# reflow_oven_main.net
KiCad netlist of a schematic drawn in EAGLE
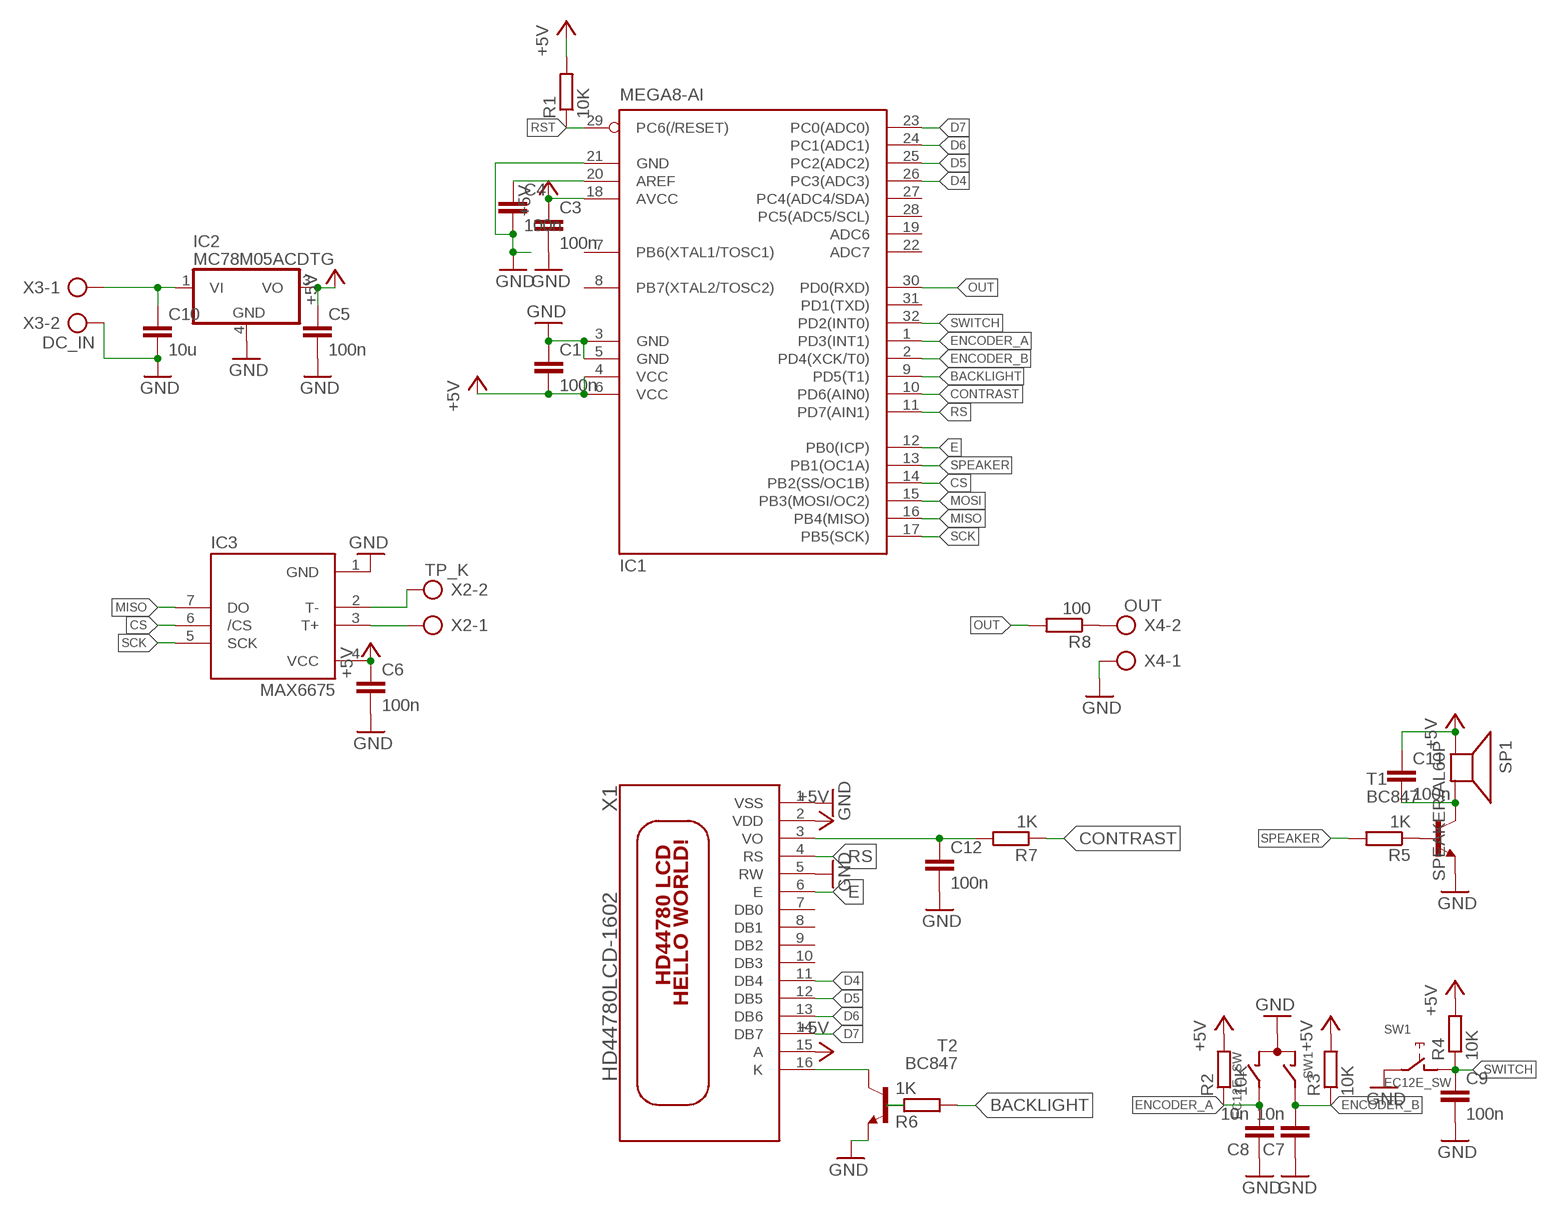
[diagram p0: schematic, sheet 1]

(export (version "E")
  (design (tool "Eeschema 10.0.6"))
  (components
    (comp (ref "C1")
      (value "100n")
      (footprint "eagle-import:C0603")
      (libsource (lib "eagle-import") (part "C-EUC0603"))
    )
    (comp (ref "C3")
      (value "100n")
      (footprint "eagle-import:C0603")
      (libsource (lib "eagle-import") (part "C-EUC0603"))
    )
    (comp (ref "C4")
      (value "100n")
      (footprint "eagle-import:C0603")
      (libsource (lib "eagle-import") (part "C-EUC0603"))
    )
    (comp (ref "C5")
      (value "100n")
      (footprint "eagle-import:C0603")
      (libsource (lib "eagle-import") (part "C-EUC0603"))
    )
    (comp (ref "C6")
      (value "100n")
      (footprint "eagle-import:C0603")
      (libsource (lib "eagle-import") (part "C-EUC0603"))
    )
    (comp (ref "C7")
      (value "10n")
      (footprint "eagle-import:C0603")
      (libsource (lib "eagle-import") (part "C-EUC0603"))
    )
    (comp (ref "C8")
      (value "10n")
      (footprint "eagle-import:C0603")
      (libsource (lib "eagle-import") (part "C-EUC0603"))
    )
    (comp (ref "C9")
      (value "100n")
      (footprint "eagle-import:C0603")
      (libsource (lib "eagle-import") (part "C-EUC0603"))
    )
    (comp (ref "C10")
      (value "10u")
      (footprint "eagle-import:C0805")
      (libsource (lib "eagle-import") (part "C-EUC0805"))
    )
    (comp (ref "C11")
      (value "100n")
      (footprint "eagle-import:C0603")
      (libsource (lib "eagle-import") (part "C-EUC0603"))
    )
    (comp (ref "C12")
      (value "100n")
      (footprint "eagle-import:C0603")
      (libsource (lib "eagle-import") (part "C-EUC0603"))
    )
    (comp (ref "IC1")
      (value "MEGA8-AI")
      (footprint "eagle-import:TQFP32-08")
      (fields (field (name "MPN") "ATMEGA8-16AU"))
      (libsource (lib "eagle-import") (part "MEGA8-AI"))
    )
    (comp (ref "IC2")
      (value "MC78M05ACDTG")
      (footprint "eagle-import:DPACK_3")
      (libsource (lib "eagle-import") (part "MC78M05ACDTG"))
    )
    (comp (ref "IC3")
      (value "MAX6675")
      (footprint "eagle-import:SO08")
      (libsource (lib "eagle-import") (part "MAX6675"))
    )
    (comp (ref "R1")
      (value "10K")
      (footprint "eagle-import:R0603")
      (libsource (lib "eagle-import") (part "R-EU_R0603"))
    )
    (comp (ref "R2")
      (value "10K")
      (footprint "eagle-import:R0603")
      (libsource (lib "eagle-import") (part "R-EU_R0603"))
    )
    (comp (ref "R3")
      (value "10K")
      (footprint "eagle-import:R0603")
      (libsource (lib "eagle-import") (part "R-EU_R0603"))
    )
    (comp (ref "R4")
      (value "10K")
      (footprint "eagle-import:R0603")
      (libsource (lib "eagle-import") (part "R-EU_R0603"))
    )
    (comp (ref "R5")
      (value "1K")
      (footprint "eagle-import:R0603")
      (libsource (lib "eagle-import") (part "R-EU_R0603"))
    )
    (comp (ref "R6")
      (value "1K")
      (footprint "eagle-import:R0603")
      (libsource (lib "eagle-import") (part "R-EU_R0603"))
    )
    (comp (ref "R7")
      (value "1K")
      (footprint "eagle-import:R0603")
      (libsource (lib "eagle-import") (part "R-EU_R0603"))
    )
    (comp (ref "R8")
      (value "100")
      (footprint "eagle-import:R0603")
      (libsource (lib "eagle-import") (part "R-EU_R0603"))
    )
    (comp (ref "SP1")
      (value "SPEAKER/AL60P")
      (footprint "eagle-import:AL60P")
      (libsource (lib "eagle-import") (part "SPEAKER/AL60P"))
    )
    (comp (ref "SW1")
      (value "EC12E_SW")
      (footprint "eagle-import:ALPS_EC12E_SW")
      (fields (field (name "MPN") "EC12E2424407"))
      (libsource (lib "eagle-import") (part "EC12E_SW"))
    )
    (comp (ref "T1")
      (value "BC847")
      (footprint "eagle-import:SOT23")
      (libsource (lib "eagle-import") (part "BC847"))
    )
    (comp (ref "T2")
      (value "BC847")
      (footprint "eagle-import:SOT23")
      (libsource (lib "eagle-import") (part "BC847"))
    )
    (comp (ref "X1")
      (value "HD44780LCD-1602")
      (footprint "eagle-import:LCD1602")
      (libsource (lib "eagle-import") (part "HD44780LCD-1602"))
    )
    (comp (ref "X2")
      (value "TP_K")
      (footprint "eagle-import:AK500_2")
      (libsource (lib "eagle-import") (part "AK500/2"))
    )
    (comp (ref "X3")
      (value "DC_IN")
      (footprint "eagle-import:AK500_2")
      (libsource (lib "eagle-import") (part "AK500/2"))
    )
    (comp (ref "X4")
      (value "OUT")
      (footprint "eagle-import:AK500_2")
      (libsource (lib "eagle-import") (part "AK500/2"))
    )
  )
  (nets
    (net (code "1") (name "+5V") (class "Default")
      (node (ref "C1") (pin "2") (pinfunction "2_2") (pintype "passive"))
      (node (ref "C11") (pin "1") (pinfunction "1_1") (pintype "passive"))
      (node (ref "C3") (pin "1") (pinfunction "1_1") (pintype "passive"))
      (node (ref "C5") (pin "1") (pinfunction "1_1") (pintype "passive"))
      (node (ref "C6") (pin "1") (pinfunction "1_1") (pintype "passive"))
      (node (ref "IC1") (pin "18") (pinfunction "AVCC_18") (pintype "power_in"))
      (node (ref "IC1") (pin "4") (pinfunction "VCC_4") (pintype "power_in"))
      (node (ref "IC1") (pin "6") (pinfunction "VCC_6") (pintype "power_in"))
      (node (ref "IC2") (pin "3") (pinfunction "VO_3") (pintype "passive"))
      (node (ref "IC3") (pin "4") (pinfunction "VCC_4") (pintype "power_in"))
      (node (ref "R1") (pin "2") (pinfunction "2_2") (pintype "passive"))
      (node (ref "R2") (pin "2") (pinfunction "2_2") (pintype "passive"))
      (node (ref "R3") (pin "2") (pinfunction "2_2") (pintype "passive"))
      (node (ref "R4") (pin "2") (pinfunction "2_2") (pintype "passive"))
      (node (ref "SP1") (pin "1") (pinfunction "+_1") (pintype "passive"))
      (node (ref "X1") (pin "15") (pinfunction "A_15") (pintype "input"))
      (node (ref "X1") (pin "2") (pinfunction "VDD_2") (pintype "power_in"))
    )
    (net (code "2") (name "BACKLIGHT") (class "Default")
      (node (ref "IC1") (pin "9") (pinfunction "PD5(T1)_9") (pintype "bidirectional"))
      (node (ref "R6") (pin "2") (pinfunction "2_2") (pintype "passive"))
    )
    (net (code "3") (name "CONTRAST") (class "Default")
      (node (ref "IC1") (pin "10") (pinfunction "PD6(AIN0)_10") (pintype "bidirectional"))
      (node (ref "R7") (pin "1") (pinfunction "1_1") (pintype "passive"))
    )
    (net (code "4") (name "CS") (class "Default")
      (node (ref "IC1") (pin "14") (pinfunction "PB2(SS/OC1B)_14") (pintype "bidirectional"))
      (node (ref "IC3") (pin "6") (pinfunction "/CS_6") (pintype "input"))
    )
    (net (code "5") (name "D4") (class "Default")
      (node (ref "IC1") (pin "26") (pinfunction "PC3(ADC3)_26") (pintype "bidirectional"))
      (node (ref "X1") (pin "11") (pinfunction "DB4_11") (pintype "bidirectional"))
    )
    (net (code "6") (name "D5") (class "Default")
      (node (ref "IC1") (pin "25") (pinfunction "PC2(ADC2)_25") (pintype "bidirectional"))
      (node (ref "X1") (pin "12") (pinfunction "DB5_12") (pintype "bidirectional"))
    )
    (net (code "7") (name "D6") (class "Default")
      (node (ref "IC1") (pin "24") (pinfunction "PC1(ADC1)_24") (pintype "bidirectional"))
      (node (ref "X1") (pin "13") (pinfunction "DB6_13") (pintype "bidirectional"))
    )
    (net (code "8") (name "D7") (class "Default")
      (node (ref "IC1") (pin "23") (pinfunction "PC0(ADC0)_23") (pintype "bidirectional"))
      (node (ref "X1") (pin "14") (pinfunction "DB7_14") (pintype "bidirectional"))
    )
    (net (code "9") (name "E") (class "Default")
      (node (ref "IC1") (pin "12") (pinfunction "PB0(ICP)_12") (pintype "bidirectional"))
      (node (ref "X1") (pin "6") (pinfunction "E_6") (pintype "input"))
    )
    (net (code "10") (name "ENCODER_A") (class "Default")
      (node (ref "C8") (pin "2") (pinfunction "2_2") (pintype "passive"))
      (node (ref "IC1") (pin "1") (pinfunction "PD3(INT1)_1") (pintype "bidirectional"))
      (node (ref "R2") (pin "1") (pinfunction "1_1") (pintype "passive"))
      (node (ref "SW1") (pin "B") (pinfunction "B_B") (pintype "passive"))
    )
    (net (code "11") (name "ENCODER_B") (class "Default")
      (node (ref "C7") (pin "2") (pinfunction "2_2") (pintype "passive"))
      (node (ref "IC1") (pin "2") (pinfunction "PD4(XCK/T0)_2") (pintype "bidirectional"))
      (node (ref "R3") (pin "1") (pinfunction "1_1") (pintype "passive"))
      (node (ref "SW1") (pin "A") (pinfunction "A_A") (pintype "passive"))
    )
    (net (code "12") (name "GND") (class "Default")
      (node (ref "C1") (pin "1") (pinfunction "1_1") (pintype "passive"))
      (node (ref "C10") (pin "2") (pinfunction "2_2") (pintype "passive"))
      (node (ref "C12") (pin "2") (pinfunction "2_2") (pintype "passive"))
      (node (ref "C3") (pin "2") (pinfunction "2_2") (pintype "passive"))
      (node (ref "C4") (pin "2") (pinfunction "2_2") (pintype "passive"))
      (node (ref "C5") (pin "2") (pinfunction "2_2") (pintype "passive"))
      (node (ref "C6") (pin "2") (pinfunction "2_2") (pintype "passive"))
      (node (ref "C7") (pin "1") (pinfunction "1_1") (pintype "passive"))
      (node (ref "C8") (pin "1") (pinfunction "1_1") (pintype "passive"))
      (node (ref "C9") (pin "2") (pinfunction "2_2") (pintype "passive"))
      (node (ref "IC1") (pin "21") (pinfunction "GND_21") (pintype "power_in"))
      (node (ref "IC1") (pin "3") (pinfunction "GND_3") (pintype "power_in"))
      (node (ref "IC1") (pin "5") (pinfunction "GND_5") (pintype "power_in"))
      (node (ref "IC2") (pin "4") (pinfunction "GND_4") (pintype "passive"))
      (node (ref "IC3") (pin "1") (pinfunction "GND_1") (pintype "power_in"))
      (node (ref "SW1") (pin "C") (pinfunction "C_C") (pintype "passive"))
      (node (ref "SW1") (pin "E") (pinfunction "2_E") (pintype "passive"))
      (node (ref "T1") (pin "2") (pinfunction "E_2") (pintype "passive"))
      (node (ref "T2") (pin "2") (pinfunction "E_2") (pintype "passive"))
      (node (ref "X1") (pin "1") (pinfunction "VSS_1") (pintype "power_in"))
      (node (ref "X1") (pin "5") (pinfunction "RW_5") (pintype "input"))
      (node (ref "X3") (pin "2") (pinfunction "KL_2") (pintype "passive"))
      (node (ref "X4") (pin "1") (pinfunction "KL_1") (pintype "passive"))
    )
    (net (code "13") (name "MISO") (class "Default")
      (node (ref "IC1") (pin "16") (pinfunction "PB4(MISO)_16") (pintype "bidirectional"))
      (node (ref "IC3") (pin "7") (pinfunction "DO_7") (pintype "output"))
    )
    (net (code "14") (name "MOSI") (class "Default")
      (node (ref "IC1") (pin "15") (pinfunction "PB3(MOSI/OC2)_15") (pintype "bidirectional"))
    )
    (net (code "15") (name "Net-(IC1-AREF)") (class "Default")
      (node (ref "C4") (pin "1") (pinfunction "1_1") (pintype "passive"))
      (node (ref "IC1") (pin "20") (pinfunction "AREF_20") (pintype "passive"))
    )
    (net (code "16") (name "Net-(IC2-VI)") (class "Default")
      (node (ref "C10") (pin "1") (pinfunction "1_1") (pintype "passive"))
      (node (ref "IC2") (pin "1") (pinfunction "VI_1") (pintype "input"))
      (node (ref "X3") (pin "1") (pinfunction "KL_1") (pintype "passive"))
    )
    (net (code "17") (name "Net-(IC3-T+)") (class "Default")
      (node (ref "IC3") (pin "3") (pinfunction "T+_3") (pintype "input"))
      (node (ref "X2") (pin "1") (pinfunction "KL_1") (pintype "passive"))
    )
    (net (code "18") (name "Net-(IC3-T-)") (class "Default")
      (node (ref "IC3") (pin "2") (pinfunction "T-_2") (pintype "input"))
      (node (ref "X2") (pin "2") (pinfunction "KL_2") (pintype "passive"))
    )
    (net (code "19") (name "Net-(SP1--)") (class "Default")
      (node (ref "C11") (pin "2") (pinfunction "2_2") (pintype "passive"))
      (node (ref "SP1") (pin "2") (pinfunction "-_2") (pintype "passive"))
      (node (ref "T1") (pin "3") (pinfunction "C_3") (pintype "passive"))
    )
    (net (code "20") (name "Net-(T1-B)") (class "Default")
      (node (ref "R5") (pin "1") (pinfunction "1_1") (pintype "passive"))
      (node (ref "T1") (pin "1") (pinfunction "B_1") (pintype "passive"))
    )
    (net (code "21") (name "Net-(T2-B)") (class "Default")
      (node (ref "R6") (pin "1") (pinfunction "1_1") (pintype "passive"))
      (node (ref "T2") (pin "1") (pinfunction "B_1") (pintype "passive"))
    )
    (net (code "22") (name "Net-(T2-C)") (class "Default")
      (node (ref "T2") (pin "3") (pinfunction "C_3") (pintype "passive"))
      (node (ref "X1") (pin "16") (pinfunction "K_16") (pintype "input"))
    )
    (net (code "23") (name "Net-(X1-VO)") (class "Default")
      (node (ref "C12") (pin "1") (pinfunction "1_1") (pintype "passive"))
      (node (ref "R7") (pin "2") (pinfunction "2_2") (pintype "passive"))
      (node (ref "X1") (pin "3") (pinfunction "VO_3") (pintype "input"))
    )
    (net (code "24") (name "Net-(X4B-KL)") (class "Default")
      (node (ref "R8") (pin "1") (pinfunction "1_1") (pintype "passive"))
      (node (ref "X4") (pin "2") (pinfunction "KL_2") (pintype "passive"))
    )
    (net (code "25") (name "OUT") (class "Default")
      (node (ref "IC1") (pin "30") (pinfunction "PD0(RXD)_30") (pintype "bidirectional"))
      (node (ref "R8") (pin "2") (pinfunction "2_2") (pintype "passive"))
    )
    (net (code "26") (name "RS") (class "Default")
      (node (ref "IC1") (pin "11") (pinfunction "PD7(AIN1)_11") (pintype "bidirectional"))
      (node (ref "X1") (pin "4") (pinfunction "RS_4") (pintype "input"))
    )
    (net (code "27") (name "RST") (class "Default")
      (node (ref "IC1") (pin "29") (pinfunction "PC6(/RESET)_29") (pintype "bidirectional"))
      (node (ref "R1") (pin "1") (pinfunction "1_1") (pintype "passive"))
    )
    (net (code "28") (name "SCK") (class "Default")
      (node (ref "IC1") (pin "17") (pinfunction "PB5(SCK)_17") (pintype "bidirectional"))
      (node (ref "IC3") (pin "5") (pinfunction "SCK_5") (pintype "input"))
    )
    (net (code "29") (name "SPEAKER") (class "Default")
      (node (ref "IC1") (pin "13") (pinfunction "PB1(OC1A)_13") (pintype "bidirectional"))
      (node (ref "R5") (pin "2") (pinfunction "2_2") (pintype "passive"))
    )
    (net (code "30") (name "SWITCH") (class "Default")
      (node (ref "C9") (pin "1") (pinfunction "1_1") (pintype "passive"))
      (node (ref "IC1") (pin "32") (pinfunction "PD2(INT0)_32") (pintype "bidirectional"))
      (node (ref "R4") (pin "1") (pinfunction "1_1") (pintype "passive"))
      (node (ref "SW1") (pin "D") (pinfunction "1_D") (pintype "passive"))
    )
    (net (code "31") (name "unconnected-(IC1-ADC6-Pad19)") (class "Default")
      (node (ref "IC1") (pin "19") (pinfunction "ADC6_19") (pintype "bidirectional"))
    )
    (net (code "32") (name "unconnected-(IC1-ADC7-Pad22)") (class "Default")
      (node (ref "IC1") (pin "22") (pinfunction "ADC7_22") (pintype "bidirectional"))
    )
    (net (code "33") (name "unconnected-(IC1-PB6(XTAL1{slash}TOSC1)-Pad7)") (class "Default")
      (node (ref "IC1") (pin "7") (pinfunction "PB6(XTAL1/TOSC1)_7") (pintype "bidirectional"))
    )
    (net (code "34") (name "unconnected-(IC1-PB7(XTAL2{slash}TOSC2)-Pad8)") (class "Default")
      (node (ref "IC1") (pin "8") (pinfunction "PB7(XTAL2/TOSC2)_8") (pintype "bidirectional"))
    )
    (net (code "35") (name "unconnected-(IC1-PC4(ADC4{slash}SDA)-Pad27)") (class "Default")
      (node (ref "IC1") (pin "27") (pinfunction "PC4(ADC4/SDA)_27") (pintype "bidirectional"))
    )
    (net (code "36") (name "unconnected-(IC1-PC5(ADC5{slash}SCL)-Pad28)") (class "Default")
      (node (ref "IC1") (pin "28") (pinfunction "PC5(ADC5/SCL)_28") (pintype "bidirectional"))
    )
    (net (code "37") (name "unconnected-(IC1-PD1(TXD)-Pad31)") (class "Default")
      (node (ref "IC1") (pin "31") (pinfunction "PD1(TXD)_31") (pintype "bidirectional"))
    )
    (net (code "38") (name "unconnected-(X1-DB0-Pad7)") (class "Default")
      (node (ref "X1") (pin "7") (pinfunction "DB0_7") (pintype "bidirectional"))
    )
    (net (code "39") (name "unconnected-(X1-DB1-Pad8)") (class "Default")
      (node (ref "X1") (pin "8") (pinfunction "DB1_8") (pintype "bidirectional"))
    )
    (net (code "40") (name "unconnected-(X1-DB2-Pad9)") (class "Default")
      (node (ref "X1") (pin "9") (pinfunction "DB2_9") (pintype "bidirectional"))
    )
    (net (code "41") (name "unconnected-(X1-DB3-Pad10)") (class "Default")
      (node (ref "X1") (pin "10") (pinfunction "DB3_10") (pintype "bidirectional"))
    )
  )
)
